# mini_Quad_v01.net
KiCad netlist of a schematic drawn in EAGLE
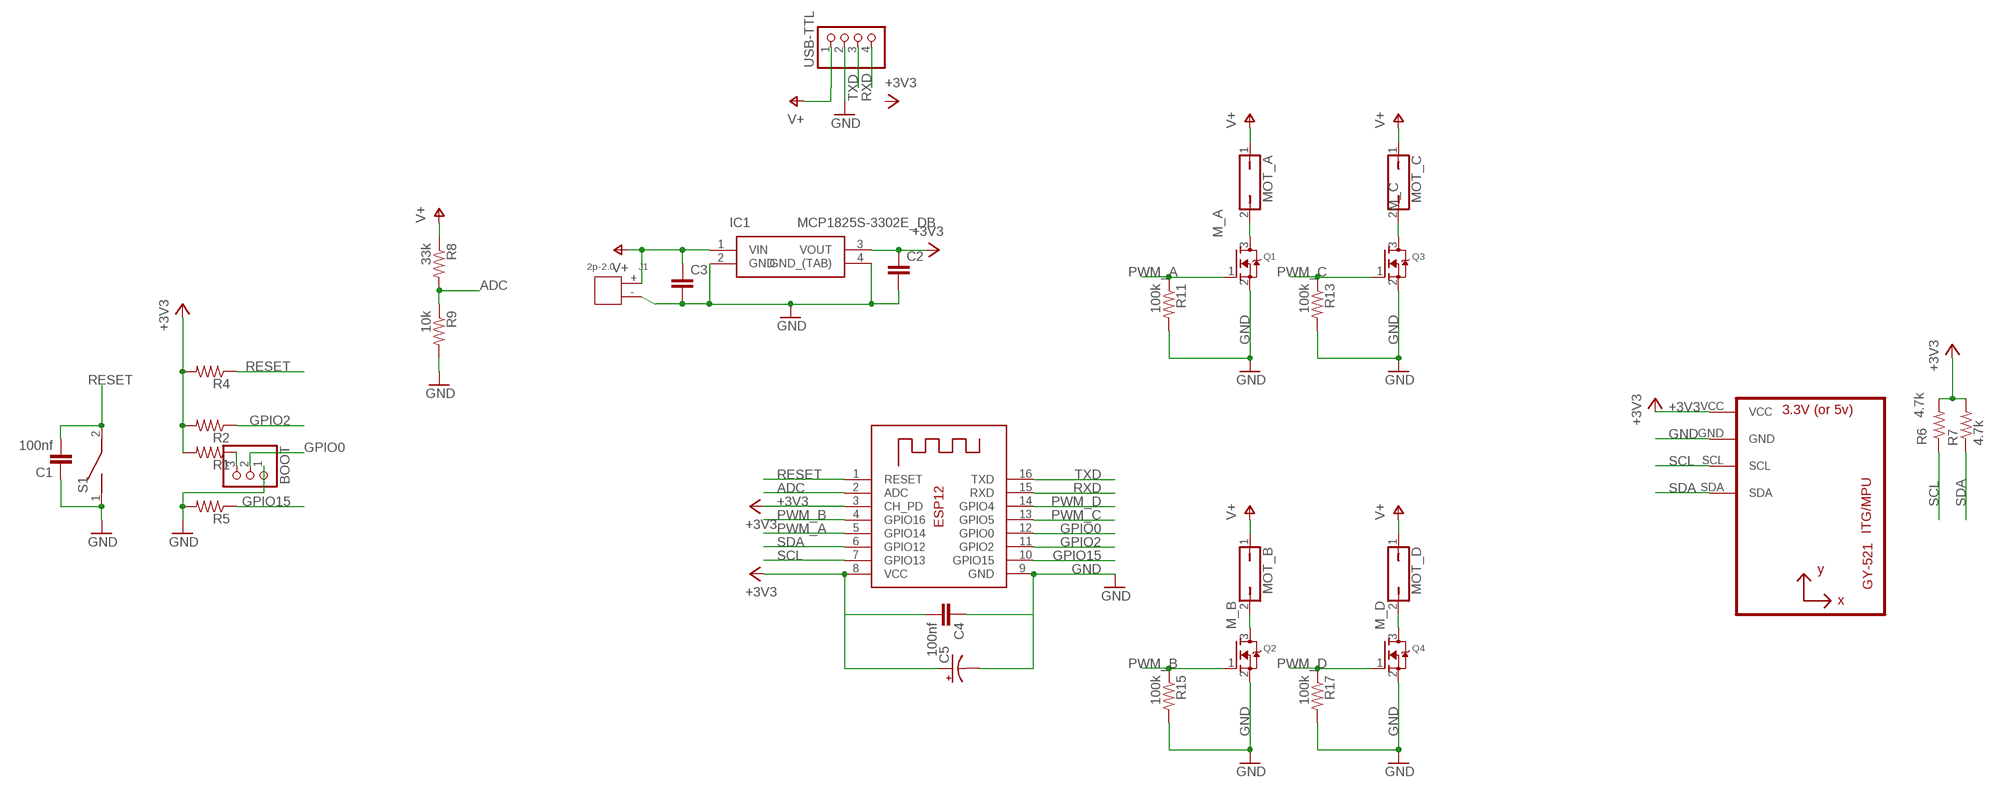
[diagram p0: schematic, sheet 1]

(export (version "E")
  (design (tool "Eeschema 10.0.6"))
  (components
    (comp (ref "BOOT")
      (value "PINHD-1X3")
      (footprint "eagle-import:1X03")
      (libsource (lib "eagle-import") (part "PINHD-1X3"))
    )
    (comp (ref "C1")
      (value "100nf")
      (footprint "eagle-import:C050-024X044")
      (libsource (lib "eagle-import") (part "C-EU050-024X044"))
    )
    (comp (ref "C2")
      (value "C-EUC1206K")
      (footprint "eagle-import:C1206K")
      (libsource (lib "eagle-import") (part "rcl_334_C-EUC1206K"))
    )
    (comp (ref "C3")
      (value "C-EUC1206K")
      (footprint "eagle-import:C1206K")
      (libsource (lib "eagle-import") (part "rcl_334_C-EUC1206K"))
    )
    (comp (ref "C4")
      (value "100nf")
      (footprint "eagle-import:C050-024X044")
      (libsource (lib "eagle-import") (part "C-EU050-024X044"))
    )
    (comp (ref "C5")
      (value "CPOL-USB/3528-21W")
      (footprint "eagle-import:B_3528-21W")
      (libsource (lib "eagle-import") (part "CPOL-USB/3528-21W"))
    )
    (comp (ref "IC1")
      (value "MCP1825S-3302E_DB")
      (footprint "eagle-import:SOT230P700X180-4N")
      (fields
        (field (name "ARROW_PART_NUMBER") "MCP1825S-3302E/DB")
        (field (name "RS_PART_NUMBER") "9115520")
      )
      (libsource (lib "eagle-import") (part "MCP1825S-3302E_DB"))
    )
    (comp (ref "J1")
      (value "2p-2.0")
      (footprint "eagle-import:H2-2.0-6X4.5MM")
      (libsource (lib "eagle-import") (part "DIP-JST-2P-2.0"))
    )
    (comp (ref "MOT_A")
      (value "JP1Q")
      (footprint "eagle-import:JP1")
      (libsource (lib "eagle-import") (part "JP1Q"))
    )
    (comp (ref "MOT_B")
      (value "JP1Q")
      (footprint "eagle-import:JP1")
      (libsource (lib "eagle-import") (part "JP1Q"))
    )
    (comp (ref "MOT_C")
      (value "JP1Q")
      (footprint "eagle-import:JP1")
      (libsource (lib "eagle-import") (part "JP1Q"))
    )
    (comp (ref "MOT_D")
      (value "JP1Q")
      (footprint "eagle-import:JP1")
      (libsource (lib "eagle-import") (part "JP1Q"))
    )
    (comp (ref "Q1")
      (value "MOSFET-NTO252")
      (footprint "eagle-import:TO252")
      (libsource (lib "eagle-import") (part "MOSFET-NTO252"))
    )
    (comp (ref "Q2")
      (value "MOSFET-NTO252")
      (footprint "eagle-import:TO252")
      (libsource (lib "eagle-import") (part "MOSFET-NTO252"))
    )
    (comp (ref "Q3")
      (value "MOSFET-NTO252")
      (footprint "eagle-import:TO252")
      (libsource (lib "eagle-import") (part "MOSFET-NTO252"))
    )
    (comp (ref "Q4")
      (value "MOSFET-NTO252")
      (footprint "eagle-import:TO252")
      (libsource (lib "eagle-import") (part "MOSFET-NTO252"))
    )
    (comp (ref "R1")
      (value "R-US_R1206W")
      (footprint "eagle-import:R1206W")
      (libsource (lib "eagle-import") (part "R-US_R1206W"))
    )
    (comp (ref "R2")
      (value "R-US_0204/5")
      (footprint "eagle-import:0204_5")
      (libsource (lib "eagle-import") (part "R-US_0204/5"))
    )
    (comp (ref "R4")
      (value "R-US_0204/7")
      (footprint "eagle-import:0204_7")
      (libsource (lib "eagle-import") (part "R-US_0204/7"))
    )
    (comp (ref "R5")
      (value "R-US_0204/5")
      (footprint "eagle-import:0204_5")
      (libsource (lib "eagle-import") (part "R-US_0204/5"))
    )
    (comp (ref "R6")
      (value "4.7k")
      (footprint "eagle-import:0204_5")
      (libsource (lib "eagle-import") (part "R-US_0204/5"))
    )
    (comp (ref "R7")
      (value "4.7k")
      (footprint "eagle-import:0204_7")
      (libsource (lib "eagle-import") (part "R-US_0204/7"))
    )
    (comp (ref "R8")
      (value "33k")
      (footprint "eagle-import:0207_10")
      (libsource (lib "eagle-import") (part "R-US_0207/10"))
    )
    (comp (ref "R9")
      (value "10k")
      (footprint "eagle-import:0204_5")
      (libsource (lib "eagle-import") (part "R-US_0204/5"))
    )
    (comp (ref "R11")
      (value "100k")
      (footprint "eagle-import:0204_5")
      (libsource (lib "eagle-import") (part "R-US_0204/5"))
    )
    (comp (ref "R13")
      (value "100k")
      (footprint "eagle-import:0204_5")
      (libsource (lib "eagle-import") (part "R-US_0204/5"))
    )
    (comp (ref "R15")
      (value "100k")
      (footprint "eagle-import:0207_10")
      (libsource (lib "eagle-import") (part "R-US_0207/10"))
    )
    (comp (ref "R17")
      (value "100k")
      (footprint "eagle-import:0204_5")
      (libsource (lib "eagle-import") (part "R-US_0204/5"))
    )
    (comp (ref "S1")
      (value "DS01")
      (footprint "eagle-import:DS-01")
      (libsource (lib "eagle-import") (part "DS01"))
    )
    (comp (ref "U1")
      (value "GY-521MPU6050")
      (footprint "eagle-import:GY-521")
      (libsource (lib "eagle-import") (part "GY-521MPU6050"))
    )
    (comp (ref "USB-TTL")
      (value "PINHD-1X4")
      (footprint "eagle-import:1X04")
      (libsource (lib "eagle-import") (part "PINHD-1X4"))
    )
    (comp (ref "X1")
      (value "ESP-12")
      (footprint "eagle-import:ESP-12")
      (libsource (lib "eagle-import") (part "ESP-12"))
    )
  )
  (nets
    (net (code "1") (name "+3V3") (class "Default")
      (node (ref "C2") (pin "1") (pinfunction "1_1") (pintype "passive"))
      (node (ref "C4") (pin "2") (pinfunction "2_2") (pintype "passive"))
      (node (ref "C5") (pin "+") (pinfunction "+_+") (pintype "passive"))
      (node (ref "IC1") (pin "3") (pinfunction "VOUT_3") (pintype "output"))
      (node (ref "R1") (pin "2") (pinfunction "2_2") (pintype "passive"))
      (node (ref "R2") (pin "2") (pinfunction "2_2") (pintype "passive"))
      (node (ref "R4") (pin "2") (pinfunction "2_2") (pintype "passive"))
      (node (ref "R6") (pin "2") (pinfunction "2_2") (pintype "passive"))
      (node (ref "R7") (pin "2") (pinfunction "2_2") (pintype "passive"))
      (node (ref "U1") (pin "VCC") (pinfunction "VCC_VCC") (pintype "bidirectional"))
      (node (ref "X1") (pin "3") (pinfunction "CH_PD_3") (pintype "input"))
      (node (ref "X1") (pin "8") (pinfunction "VCC_8") (pintype "power_in"))
    )
    (net (code "2") (name "/ADC") (class "Default")
      (node (ref "R8") (pin "2") (pinfunction "2_2") (pintype "passive"))
      (node (ref "R9") (pin "1") (pinfunction "1_1") (pintype "passive"))
      (node (ref "X1") (pin "2") (pinfunction "ADC_2") (pintype "passive"))
    )
    (net (code "3") (name "/GPIO0") (class "Default")
      (node (ref "BOOT") (pin "2") (pinfunction "2_2") (pintype "passive"))
      (node (ref "X1") (pin "12") (pinfunction "GPIO0_12") (pintype "bidirectional"))
    )
    (net (code "4") (name "/GPIO2") (class "Default")
      (node (ref "R2") (pin "1") (pinfunction "1_1") (pintype "passive"))
      (node (ref "X1") (pin "11") (pinfunction "GPIO2_11") (pintype "bidirectional"))
    )
    (net (code "5") (name "/GPIO15") (class "Default")
      (node (ref "R5") (pin "1") (pinfunction "1_1") (pintype "passive"))
      (node (ref "X1") (pin "10") (pinfunction "GPIO15_10") (pintype "bidirectional"))
    )
    (net (code "6") (name "/M_A") (class "Default")
      (node (ref "MOT_A") (pin "2") (pinfunction "2_2") (pintype "passive"))
      (node (ref "Q1") (pin "3") (pinfunction "D_3") (pintype "bidirectional"))
    )
    (net (code "7") (name "/M_B") (class "Default")
      (node (ref "MOT_B") (pin "2") (pinfunction "2_2") (pintype "passive"))
      (node (ref "Q2") (pin "3") (pinfunction "D_3") (pintype "bidirectional"))
    )
    (net (code "8") (name "/M_C") (class "Default")
      (node (ref "MOT_C") (pin "2") (pinfunction "2_2") (pintype "passive"))
      (node (ref "Q3") (pin "3") (pinfunction "D_3") (pintype "bidirectional"))
    )
    (net (code "9") (name "/M_D") (class "Default")
      (node (ref "MOT_D") (pin "2") (pinfunction "2_2") (pintype "passive"))
      (node (ref "Q4") (pin "3") (pinfunction "D_3") (pintype "bidirectional"))
    )
    (net (code "10") (name "/PWM_A") (class "Default")
      (node (ref "Q1") (pin "1") (pinfunction "G_1") (pintype "bidirectional"))
      (node (ref "R11") (pin "1") (pinfunction "1_1") (pintype "passive"))
      (node (ref "X1") (pin "5") (pinfunction "GPIO14_5") (pintype "bidirectional"))
    )
    (net (code "11") (name "/PWM_B") (class "Default")
      (node (ref "Q2") (pin "1") (pinfunction "G_1") (pintype "bidirectional"))
      (node (ref "R15") (pin "1") (pinfunction "1_1") (pintype "passive"))
      (node (ref "X1") (pin "4") (pinfunction "GPIO16_4") (pintype "bidirectional"))
    )
    (net (code "12") (name "/PWM_C") (class "Default")
      (node (ref "Q3") (pin "1") (pinfunction "G_1") (pintype "bidirectional"))
      (node (ref "R13") (pin "1") (pinfunction "1_1") (pintype "passive"))
      (node (ref "X1") (pin "13") (pinfunction "GPIO5_13") (pintype "bidirectional"))
    )
    (net (code "13") (name "/PWM_D") (class "Default")
      (node (ref "Q4") (pin "1") (pinfunction "G_1") (pintype "bidirectional"))
      (node (ref "R17") (pin "1") (pinfunction "1_1") (pintype "passive"))
      (node (ref "X1") (pin "14") (pinfunction "GPIO4_14") (pintype "bidirectional"))
    )
    (net (code "14") (name "/RESET") (class "Default")
      (node (ref "C1") (pin "2") (pinfunction "2_2") (pintype "passive"))
      (node (ref "R4") (pin "1") (pinfunction "1_1") (pintype "passive"))
      (node (ref "S1") (pin "2") (pinfunction "2_2") (pintype "passive"))
      (node (ref "X1") (pin "1") (pinfunction "RESET_1") (pintype "input"))
    )
    (net (code "15") (name "/RXD") (class "Default")
      (node (ref "USB-TTL") (pin "4") (pinfunction "4_4") (pintype "passive"))
      (node (ref "X1") (pin "15") (pinfunction "RXD_15") (pintype "input"))
    )
    (net (code "16") (name "/SCL") (class "Default")
      (node (ref "R6") (pin "1") (pinfunction "1_1") (pintype "passive"))
      (node (ref "U1") (pin "SCL") (pinfunction "SCL_SCL") (pintype "bidirectional"))
      (node (ref "X1") (pin "7") (pinfunction "GPIO13_7") (pintype "bidirectional"))
    )
    (net (code "17") (name "/SDA") (class "Default")
      (node (ref "R7") (pin "1") (pinfunction "1_1") (pintype "passive"))
      (node (ref "U1") (pin "SDA") (pinfunction "SDA_SDA") (pintype "bidirectional"))
      (node (ref "X1") (pin "6") (pinfunction "GPIO12_6") (pintype "bidirectional"))
    )
    (net (code "18") (name "/TXD") (class "Default")
      (node (ref "USB-TTL") (pin "3") (pinfunction "3_3") (pintype "passive"))
      (node (ref "X1") (pin "16") (pinfunction "TXD_16") (pintype "output"))
    )
    (net (code "19") (name "GND") (class "Default")
      (node (ref "BOOT") (pin "1") (pinfunction "1_1") (pintype "passive"))
      (node (ref "C1") (pin "1") (pinfunction "1_1") (pintype "passive"))
      (node (ref "C2") (pin "2") (pinfunction "2_2") (pintype "passive"))
      (node (ref "C3") (pin "2") (pinfunction "2_2") (pintype "passive"))
      (node (ref "C4") (pin "1") (pinfunction "1_1") (pintype "passive"))
      (node (ref "C5") (pin "-") (pinfunction "-_-") (pintype "passive"))
      (node (ref "IC1") (pin "2") (pinfunction "GND_2") (pintype "power_in"))
      (node (ref "IC1") (pin "4") (pinfunction "GND_(TAB)_4") (pintype "power_in"))
      (node (ref "J1") (pin "-") (pinfunction "P$2_-") (pintype "bidirectional"))
      (node (ref "Q1") (pin "2") (pinfunction "S_2") (pintype "bidirectional"))
      (node (ref "Q2") (pin "2") (pinfunction "S_2") (pintype "bidirectional"))
      (node (ref "Q3") (pin "2") (pinfunction "S_2") (pintype "bidirectional"))
      (node (ref "Q4") (pin "2") (pinfunction "S_2") (pintype "bidirectional"))
      (node (ref "R11") (pin "2") (pinfunction "2_2") (pintype "passive"))
      (node (ref "R13") (pin "2") (pinfunction "2_2") (pintype "passive"))
      (node (ref "R15") (pin "2") (pinfunction "2_2") (pintype "passive"))
      (node (ref "R17") (pin "2") (pinfunction "2_2") (pintype "passive"))
      (node (ref "R5") (pin "2") (pinfunction "2_2") (pintype "passive"))
      (node (ref "R9") (pin "2") (pinfunction "2_2") (pintype "passive"))
      (node (ref "S1") (pin "1") (pinfunction "1_1") (pintype "passive"))
      (node (ref "U1") (pin "GND") (pinfunction "GND_GND") (pintype "bidirectional"))
      (node (ref "USB-TTL") (pin "2") (pinfunction "2_2") (pintype "passive"))
      (node (ref "X1") (pin "9") (pinfunction "GND_9") (pintype "power_in"))
    )
    (net (code "20") (name "Net-(BOOT-Pad3)") (class "Default")
      (node (ref "BOOT") (pin "3") (pinfunction "3_3") (pintype "passive"))
      (node (ref "R1") (pin "1") (pinfunction "1_1") (pintype "passive"))
    )
    (net (code "21") (name "V+") (class "Default")
      (node (ref "C3") (pin "1") (pinfunction "1_1") (pintype "passive"))
      (node (ref "IC1") (pin "1") (pinfunction "VIN_1") (pintype "input"))
      (node (ref "J1") (pin "+") (pinfunction "P$1_+") (pintype "bidirectional"))
      (node (ref "MOT_A") (pin "1") (pinfunction "1_1") (pintype "passive"))
      (node (ref "MOT_B") (pin "1") (pinfunction "1_1") (pintype "passive"))
      (node (ref "MOT_C") (pin "1") (pinfunction "1_1") (pintype "passive"))
      (node (ref "MOT_D") (pin "1") (pinfunction "1_1") (pintype "passive"))
      (node (ref "R8") (pin "1") (pinfunction "1_1") (pintype "passive"))
      (node (ref "USB-TTL") (pin "1") (pinfunction "1_1") (pintype "passive"))
    )
  )
)
